# Main.net
KiCad netlist of a schematic drawn in Altium Designer
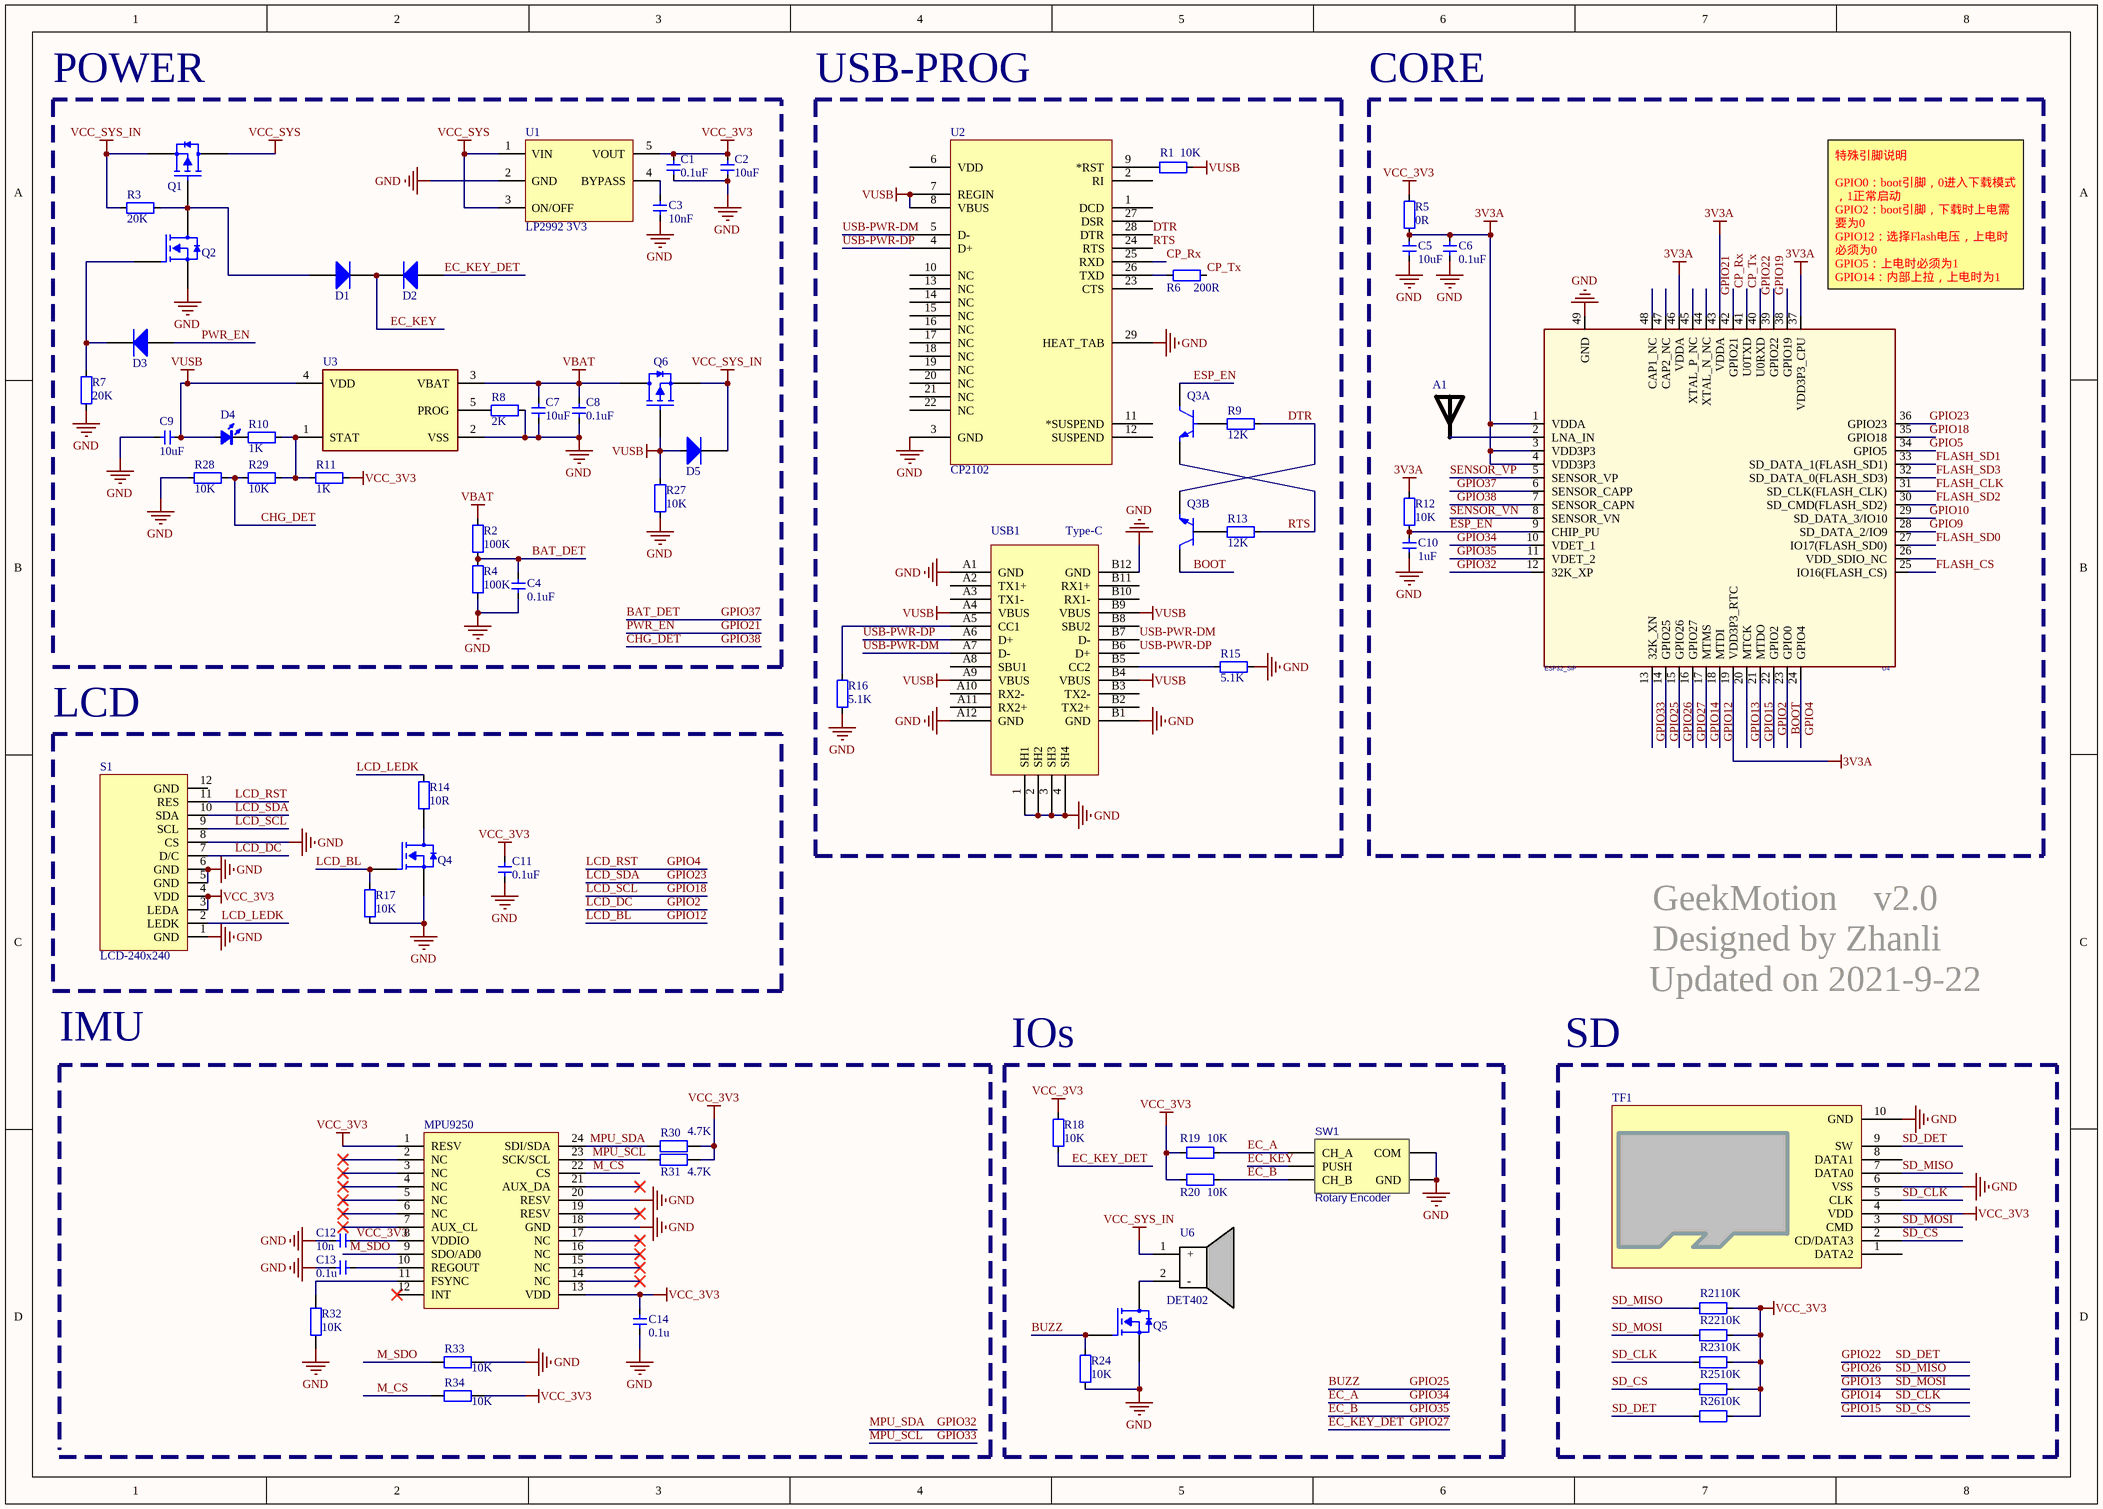
[diagram p0: Main.SchDoc]

(export (version "E")
  (design (tool "Eeschema 10.0.6"))
  (components
    (comp (ref "A1")
      (value "RAINSUN")
      (footprint "ANT-Rainsun-AN5120")
      (libsource (lib "MyPcbLib") (part "ANT-Rainsun-AP5120"))
    )
    (comp (ref "C1")
      (value "0.1uF")
      (footprint "CAP_0402")
      (description "Capacitor")
      (libsource (lib "MyPcbLib") (part "电容-0402"))
    )
    (comp (ref "C2")
      (value "10uF")
      (footprint "CAP_0402")
      (description "Capacitor")
      (libsource (lib "MyPcbLib") (part "电容-0402"))
    )
    (comp (ref "C3")
      (value "10nF")
      (footprint "CAP_0402")
      (description "Capacitor")
      (libsource (lib "MyPcbLib") (part "电容-0402"))
    )
    (comp (ref "C4")
      (value "0.1uF")
      (footprint "CAP_0402")
      (description "Capacitor")
      (libsource (lib "MyPcbLib") (part "电容-0402"))
    )
    (comp (ref "C5")
      (value "10uF")
      (footprint "CAP_0402")
      (description "Capacitor")
      (libsource (lib "MyPcbLib") (part "电容-0402"))
    )
    (comp (ref "C6")
      (value "0.1uF")
      (footprint "CAP_0402")
      (description "Capacitor")
      (libsource (lib "MyPcbLib") (part "电容-0402"))
    )
    (comp (ref "C7")
      (value "10uF")
      (footprint "CAP_0402")
      (description "Capacitor")
      (libsource (lib "MyPcbLib") (part "电容-0402"))
    )
    (comp (ref "C8")
      (value "0.1uF")
      (footprint "CAP_0402")
      (description "Capacitor")
      (libsource (lib "MyPcbLib") (part "电容-0402"))
    )
    (comp (ref "C9")
      (value "10uF")
      (footprint "CAP_0402")
      (description "Capacitor")
      (libsource (lib "MyPcbLib") (part "电容-0402"))
    )
    (comp (ref "C10")
      (value "1uF")
      (footprint "CAP_0402")
      (description "Capacitor")
      (libsource (lib "MyPcbLib") (part "电容-0402"))
    )
    (comp (ref "C11")
      (value "0.1uF")
      (footprint "CAP_0402")
      (description "Capacitor")
      (libsource (lib "MyPcbLib") (part "电容-0402"))
    )
    (comp (ref "C12")
      (value "10n")
      (footprint "CAP_0402")
      (description "Capacitor")
      (fields (field (name "Comment") "Cap_0603"))
      (libsource (lib "SmartIMU") (part "Cap_0603"))
    )
    (comp (ref "C13")
      (value "0.1u")
      (footprint "CAP_0402")
      (description "Capacitor")
      (fields (field (name "Comment") "Cap_0603"))
      (libsource (lib "SmartIMU") (part "Cap_0603"))
    )
    (comp (ref "C14")
      (value "0.1u")
      (footprint "CAP_0402")
      (description "Capacitor")
      (fields (field (name "Comment") "Cap_0603"))
      (libsource (lib "SmartIMU") (part "Cap_0603"))
    )
    (comp (ref "D1")
      (value "二极管-5819W")
      (footprint "SOD-323")
      (description "40V")
      (libsource (lib "MyPcbLib") (part "二极管-5819W"))
    )
    (comp (ref "D2")
      (value "二极管-5819W")
      (footprint "SOD-323")
      (description "40V")
      (libsource (lib "MyPcbLib") (part "二极管-5819W"))
    )
    (comp (ref "D3")
      (value "二极管-5819W")
      (footprint "SOD-323")
      (description "40V")
      (libsource (lib "MyPcbLib") (part "二极管-5819W"))
    )
    (comp (ref "D4")
      (value "color?")
      (footprint "LED_0402_RED")
      (description "LED")
      (libsource (lib "KitSprout") (part "LED_0402"))
    )
    (comp (ref "D5")
      (value "二极管-5819W")
      (footprint "SOD-323")
      (description "40V")
      (libsource (lib "Peak") (part "二极管-5819W"))
    )
    (comp (ref "MPU9250")
      (value "MPU9250")
      (footprint "GeekIMUv1:QFN_P0.4_24")
      (description "Sensor Motion")
      (libsource (lib "GeekIMU") (part "MPU925x"))
    )
    (comp (ref "Q1")
      (value "AO3401A")
      (footprint "SOT23-3")
      (description "P-MOS")
      (libsource (lib "MyPcbLib") (part "AO3401A"))
    )
    (comp (ref "Q2")
      (value "AO3400A")
      (footprint "SOT23-3")
      (description "N-MOS")
      (libsource (lib "MyPcbLib") (part "AO3400A"))
    )
    (comp (ref "Q3")
      (value "BC847BVC-7")
      (footprint "SOT563-6")
      (libsource (lib "MyPcbLib") (part "BC847BVC-7"))
    )
    (comp (ref "Q4")
      (value "AO3400A")
      (footprint "SOT23-3")
      (description "N-MOS")
      (libsource (lib "MyPcbLib") (part "AO3400A"))
    )
    (comp (ref "Q5")
      (value "AO3400A")
      (footprint "SOT23-3")
      (description "N-MOS")
      (libsource (lib "MyPcbLib") (part "AO3400A"))
    )
    (comp (ref "Q6")
      (value "AO3401A")
      (footprint "SOT23-3")
      (description "P-MOS")
      (libsource (lib "MyPcbLib") (part "AO3401A"))
    )
    (comp (ref "R1")
      (value "10K")
      (footprint "RES_0402")
      (description "Resistor")
      (libsource (lib "") (part "电阻-0402_1"))
    )
    (comp (ref "R2")
      (value "100K")
      (footprint "RES_0402")
      (description "Resistor")
      (libsource (lib "") (part "电阻-0402_2"))
    )
    (comp (ref "R3")
      (value "20K")
      (footprint "RES_0402")
      (description "Resistor")
      (libsource (lib "MyPcbLib") (part "电阻-0402"))
    )
    (comp (ref "R4")
      (value "100K")
      (footprint "RES_0402")
      (description "Resistor")
      (libsource (lib "") (part "电阻-0402_2"))
    )
    (comp (ref "R5")
      (value "0R")
      (footprint "RES_0402")
      (description "Resistor")
      (libsource (lib "") (part "电阻-0402_3"))
    )
    (comp (ref "R6")
      (value "200R")
      (footprint "RES_0402")
      (description "Resistor")
      (libsource (lib "") (part "电阻-0402_1"))
    )
    (comp (ref "R7")
      (value "20K")
      (footprint "RES_0402")
      (description "Resistor")
      (libsource (lib "") (part "电阻-0402_2"))
    )
    (comp (ref "R8")
      (value "2K")
      (footprint "RES_0402")
      (description "Resistor")
      (libsource (lib "MyPcbLib") (part "电阻-0402"))
    )
    (comp (ref "R9")
      (value "12K")
      (footprint "RES_0402")
      (description "Resistor")
      (libsource (lib "") (part "电阻-0402_1"))
    )
    (comp (ref "R10")
      (value "1K")
      (footprint "RES_0402")
      (description "Resistor")
      (libsource (lib "MyPcbLib") (part "电阻-0402"))
    )
    (comp (ref "R11")
      (value "1K")
      (footprint "RES_0402")
      (description "Resistor")
      (libsource (lib "MyPcbLib") (part "电阻-0402"))
    )
    (comp (ref "R12")
      (value "10K")
      (footprint "RES_0402")
      (description "Resistor")
      (libsource (lib "") (part "电阻-0402_3"))
    )
    (comp (ref "R13")
      (value "12K")
      (footprint "RES_0402")
      (description "Resistor")
      (libsource (lib "") (part "电阻-0402_1"))
    )
    (comp (ref "R14")
      (value "10R")
      (footprint "RES_0402")
      (description "Resistor")
      (libsource (lib "") (part "电阻-0402_2"))
    )
    (comp (ref "R15")
      (value "5.1K")
      (footprint "RES_0402")
      (description "Resistor")
      (libsource (lib "") (part "电阻-0402_1"))
    )
    (comp (ref "R16")
      (value "5.1K")
      (footprint "RES_0402")
      (description "Resistor")
      (libsource (lib "") (part "电阻-0402_3"))
    )
    (comp (ref "R17")
      (value "10K")
      (footprint "RES_0402")
      (description "Resistor")
      (libsource (lib "") (part "电阻-0402_2"))
    )
    (comp (ref "R18")
      (value "10K")
      (footprint "RES_0402")
      (description "Resistor")
      (libsource (lib "") (part "电阻-0402_3"))
    )
    (comp (ref "R19")
      (value "10K")
      (footprint "RES_0402")
      (description "Resistor")
      (libsource (lib "") (part "电阻-0402_1"))
    )
    (comp (ref "R20")
      (value "10K")
      (footprint "RES_0402")
      (description "Resistor")
      (libsource (lib "") (part "电阻-0402_1"))
    )
    (comp (ref "R21")
      (value "10K")
      (footprint "RES_0402")
      (description "Resistor")
      (libsource (lib "") (part "电阻-0402_1"))
    )
    (comp (ref "R22")
      (value "10K")
      (footprint "RES_0402")
      (description "Resistor")
      (libsource (lib "") (part "电阻-0402_1"))
    )
    (comp (ref "R23")
      (value "10K")
      (footprint "RES_0402")
      (description "Resistor")
      (libsource (lib "") (part "电阻-0402_1"))
    )
    (comp (ref "R24")
      (value "10K")
      (footprint "RES_0402")
      (description "Resistor")
      (libsource (lib "") (part "电阻-0402_2"))
    )
    (comp (ref "R25")
      (value "10K")
      (footprint "RES_0402")
      (description "Resistor")
      (libsource (lib "") (part "电阻-0402_1"))
    )
    (comp (ref "R26")
      (value "10K")
      (footprint "RES_0402")
      (description "Resistor")
      (libsource (lib "") (part "电阻-0402_1"))
    )
    (comp (ref "R27")
      (value "10K")
      (footprint "RES_0402")
      (description "Resistor")
      (libsource (lib "") (part "电阻-0402_2"))
    )
    (comp (ref "R28")
      (value "10K")
      (footprint "Peak:RES_0402")
      (description "Resistor")
      (libsource (lib "") (part "电阻-0402_1"))
    )
    (comp (ref "R29")
      (value "10K")
      (footprint "RES_0402")
      (description "Resistor")
      (libsource (lib "") (part "电阻-0402_1"))
    )
    (comp (ref "R30")
      (value "4.7K")
      (footprint "Peak:RES_0402")
      (description "Resistor")
      (fields (field (name "PUBLISHER") "Altium Limited"))
      (libsource (lib "Peak") (part "Res2"))
    )
    (comp (ref "R31")
      (value "4.7K")
      (footprint "Peak:RES_0402")
      (description "Resistor")
      (fields (field (name "PUBLISHER") "Altium Limited"))
      (libsource (lib "Peak") (part "Res2"))
    )
    (comp (ref "R32")
      (value "10K")
      (footprint "Peak:RES_0402")
      (description "Resistor")
      (fields (field (name "PUBLISHER") "Altium Limited"))
      (libsource (lib "") (part "Res2_1"))
    )
    (comp (ref "R33")
      (value "10K")
      (footprint "Peak:RES_0402")
      (description "Resistor")
      (fields (field (name "PUBLISHER") "Altium Limited"))
      (libsource (lib "Peak") (part "Res2"))
    )
    (comp (ref "R34")
      (value "10K")
      (footprint "Peak:RES_0402")
      (description "Resistor")
      (fields (field (name "PUBLISHER") "Altium Limited"))
      (libsource (lib "Peak") (part "Res2"))
    )
    (comp (ref "S1")
      (value "LCD-240x240")
      (footprint "LCD-240x240-FlUSH-154")
      (description "显示屏")
      (libsource (lib "mLib") (part "LCD-240x240"))
    )
    (comp (ref "SW1")
      (value "Rotary Encoder")
      (footprint "SIQ-02FVS3")
      (fields
        (field (name "BOM_SUPPLIER PART") "C1322543")
        (field (name "BOM_MANUFACTURER PART") "EC11E1534443")
        (field (name "CONTRIBUTOR") "LCSC")
      )
      (libsource (lib "MyPcbLib") (part "Rotary Encoder"))
    )
    (comp (ref "TF1")
      (value "TF")
      (footprint "TF-SOCKET")
      (description "8脚自弹")
      (libsource (lib "MyPcbLib") (part "TF卡座"))
    )
    (comp (ref "U1")
      (value "LP2992 3V3")
      (footprint "SOT23-5")
      (description "LDO")
      (libsource (lib "mLib") (part "LP2992"))
    )
    (comp (ref "U2")
      (value "CP2102")
      (footprint "QFN-28")
      (description "USB转TTL")
      (libsource (lib "mLib") (part "CP2102"))
    )
    (comp (ref "U3")
      (value "MCP73831T")
      (footprint "SOT23-5")
      (libsource (lib "MyPcbLib") (part "MCP73831T"))
    )
    (comp (ref "U4")
      (value "ESP32_SIP")
      (footprint "QFN-48_7X7")
      (libsource (lib "mLib") (part "ESP32-PICO"))
    )
    (comp (ref "U6") (value "DET402") (footprint "DET402") (libsource (lib "MyPcbLib") (part "DET402")))
    (comp (ref "USB1")
      (value "Type-C")
      (footprint "Type-C-TOP")
      (libsource (lib "MyPcbLib") (part "USB-Type-C-TOP"))
    )
  )
  (nets
    (net (code "1") (name "/BAT_DET") (class "Default")
      (node (ref "C4") (pin "2") (pinfunction "2_2") (pintype "passive"))
      (node (ref "R2") (pin "1") (pinfunction "1_1") (pintype "passive"))
      (node (ref "R4") (pin "2") (pinfunction "2_2") (pintype "passive"))
      (node (ref "U4") (pin "6") (pinfunction "SENSOR_CAPP_6") (pintype "passive"))
    )
    (net (code "2") (name "/BOOT") (class "Default")
      (node (ref "Q3") (pin "3") (pinfunction "C2_3") (pintype "passive"))
      (node (ref "U4") (pin "23") (pinfunction "GPIO0_23") (pintype "passive"))
    )
    (net (code "3") (name "/BUZZ") (class "Default")
      (node (ref "Q5") (pin "1") (pinfunction "G_1") (pintype "passive"))
      (node (ref "R24") (pin "2") (pinfunction "2_2") (pintype "passive"))
      (node (ref "U4") (pin "14") (pinfunction "GPIO25_14") (pintype "passive"))
    )
    (net (code "4") (name "/CHG_DET") (class "Default")
      (node (ref "R28") (pin "1") (pinfunction "1_1") (pintype "passive"))
      (node (ref "R29") (pin "2") (pinfunction "2_2") (pintype "passive"))
      (node (ref "U4") (pin "7") (pinfunction "SENSOR_CAPN_7") (pintype "passive"))
    )
    (net (code "5") (name "/CP_Rx") (class "Default")
      (node (ref "U2") (pin "25") (pinfunction "RXD_25") (pintype "passive"))
      (node (ref "U4") (pin "41") (pinfunction "U0TXD_41") (pintype "power_in"))
    )
    (net (code "6") (name "/CP_Tx") (class "Default")
      (node (ref "R6") (pin "1") (pinfunction "1_1") (pintype "passive"))
      (node (ref "U4") (pin "40") (pinfunction "U0RXD_40") (pintype "power_in"))
    )
    (net (code "7") (name "/DTR") (class "Default")
      (node (ref "Q3") (pin "4") (pinfunction "E2_4") (pintype "passive"))
      (node (ref "R9") (pin "1") (pinfunction "1_1") (pintype "passive"))
      (node (ref "U2") (pin "28") (pinfunction "DTR_28") (pintype "passive"))
    )
    (net (code "8") (name "/EC_A") (class "Default")
      (node (ref "R19") (pin "1") (pinfunction "1_1") (pintype "passive"))
      (node (ref "SW1") (pin "1") (pinfunction "CH_A_1") (pintype "passive"))
      (node (ref "U4") (pin "10") (pinfunction "VDET_1_10") (pintype "passive"))
    )
    (net (code "9") (name "/EC_B") (class "Default")
      (node (ref "R20") (pin "1") (pinfunction "1_1") (pintype "passive"))
      (node (ref "SW1") (pin "4") (pinfunction "CH_B_4") (pintype "passive"))
      (node (ref "U4") (pin "11") (pinfunction "VDET_2_11") (pintype "passive"))
    )
    (net (code "10") (name "/EC_KEY") (class "Default")
      (node (ref "D1") (pin "2") (pinfunction "K_2") (pintype "passive"))
      (node (ref "D2") (pin "2") (pinfunction "K_2") (pintype "passive"))
      (node (ref "SW1") (pin "2") (pinfunction "PUSH_2") (pintype "passive"))
    )
    (net (code "11") (name "/EC_KEY_DET") (class "Default")
      (node (ref "D2") (pin "1") (pinfunction "A_1") (pintype "passive"))
      (node (ref "R18") (pin "2") (pinfunction "2_2") (pintype "passive"))
      (node (ref "U4") (pin "16") (pinfunction "GPIO27_16") (pintype "passive"))
    )
    (net (code "12") (name "/ESP_EN") (class "Default")
      (node (ref "C10") (pin "1") (pinfunction "1_1") (pintype "passive"))
      (node (ref "Q3") (pin "6") (pinfunction "C1_6") (pintype "passive"))
      (node (ref "R12") (pin "2") (pinfunction "2_2") (pintype "passive"))
      (node (ref "U4") (pin "9") (pinfunction "CHIP_PU_9") (pintype "passive"))
    )
    (net (code "13") (name "/FLASH_CLK") (class "Default")
      (node (ref "U4") (pin "31") (pinfunction "SD_CLK(FLASH_CLK)_31") (pintype "passive"))
    )
    (net (code "14") (name "/FLASH_CS") (class "Default")
      (node (ref "U4") (pin "25") (pinfunction "IO16(FLASH_CS)_25") (pintype "passive"))
    )
    (net (code "15") (name "/FLASH_SD0") (class "Default")
      (node (ref "U4") (pin "27") (pinfunction "IO17(FLASH_SD0)_27") (pintype "passive"))
    )
    (net (code "16") (name "/FLASH_SD1") (class "Default")
      (node (ref "U4") (pin "33") (pinfunction "SD_DATA_1(FLASH_SD1)_33") (pintype "passive"))
    )
    (net (code "17") (name "/FLASH_SD2") (class "Default")
      (node (ref "U4") (pin "30") (pinfunction "SD_CMD(FLASH_SD2)_30") (pintype "passive"))
    )
    (net (code "18") (name "/FLASH_SD3") (class "Default")
      (node (ref "U4") (pin "32") (pinfunction "SD_DATA_0(FLASH_SD3)_32") (pintype "passive"))
    )
    (net (code "19") (name "/GPIO2") (class "Default")
      (node (ref "S1") (pin "7") (pinfunction "D/C_7") (pintype "passive"))
      (node (ref "U4") (pin "22") (pinfunction "GPIO2_22") (pintype "passive"))
    )
    (net (code "20") (name "/GPIO4") (class "Default")
      (node (ref "S1") (pin "11") (pinfunction "RES_11") (pintype "passive"))
      (node (ref "U4") (pin "24") (pinfunction "GPIO4_24") (pintype "passive"))
    )
    (net (code "21") (name "/GPIO5") (class "Default")
      (node (ref "U4") (pin "34") (pinfunction "GPIO5_34") (pintype "passive"))
    )
    (net (code "22") (name "/GPIO9") (class "Default")
      (node (ref "U4") (pin "28") (pinfunction "SD_DATA_2/IO9_28") (pintype "passive"))
    )
    (net (code "23") (name "/GPIO10") (class "Default")
      (node (ref "U4") (pin "29") (pinfunction "SD_DATA_3/IO10_29") (pintype "passive"))
    )
    (net (code "24") (name "/GPIO12") (class "Default")
      (node (ref "Q4") (pin "1") (pinfunction "G_1") (pintype "passive"))
      (node (ref "R17") (pin "2") (pinfunction "2_2") (pintype "passive"))
      (node (ref "U4") (pin "18") (pinfunction "MTDI_18") (pintype "passive"))
    )
    (net (code "25") (name "/GPIO13") (class "Default")
      (node (ref "R22") (pin "2") (pinfunction "2_2") (pintype "passive"))
      (node (ref "TF1") (pin "3") (pinfunction "CMD_3") (pintype "passive"))
      (node (ref "U4") (pin "20") (pinfunction "MTCK_20") (pintype "passive"))
    )
    (net (code "26") (name "/GPIO14") (class "Default")
      (node (ref "R23") (pin "2") (pinfunction "2_2") (pintype "passive"))
      (node (ref "TF1") (pin "5") (pinfunction "CLK_5") (pintype "passive"))
      (node (ref "U4") (pin "17") (pinfunction "MTMS_17") (pintype "passive"))
    )
    (net (code "27") (name "/GPIO15") (class "Default")
      (node (ref "R25") (pin "2") (pinfunction "2_2") (pintype "passive"))
      (node (ref "TF1") (pin "2") (pinfunction "CD/DATA3_2") (pintype "passive"))
      (node (ref "U4") (pin "21") (pinfunction "MTDO_21") (pintype "passive"))
    )
    (net (code "28") (name "/GPIO18") (class "Default")
      (node (ref "S1") (pin "9") (pinfunction "SCL_9") (pintype "passive"))
      (node (ref "U4") (pin "35") (pinfunction "GPIO18_35") (pintype "passive"))
    )
    (net (code "29") (name "/GPIO19") (class "Default")
      (node (ref "U4") (pin "38") (pinfunction "GPIO19_38") (pintype "passive"))
    )
    (net (code "30") (name "/GPIO21") (class "Default")
      (node (ref "D3") (pin "1") (pinfunction "A_1") (pintype "passive"))
      (node (ref "U4") (pin "42") (pinfunction "GPIO21_42") (pintype "passive"))
    )
    (net (code "31") (name "/GPIO22") (class "Default")
      (node (ref "R26") (pin "2") (pinfunction "2_2") (pintype "passive"))
      (node (ref "TF1") (pin "9") (pinfunction "SW_9") (pintype "passive"))
      (node (ref "U4") (pin "39") (pinfunction "GPIO22_39") (pintype "passive"))
    )
    (net (code "32") (name "/GPIO23") (class "Default")
      (node (ref "S1") (pin "10") (pinfunction "SDA_10") (pintype "passive"))
      (node (ref "U4") (pin "36") (pinfunction "GPIO23_36") (pintype "passive"))
    )
    (net (code "33") (name "/GPIO26") (class "Default")
      (node (ref "R21") (pin "2") (pinfunction "2_2") (pintype "passive"))
      (node (ref "TF1") (pin "7") (pinfunction "DATA0_7") (pintype "passive"))
      (node (ref "U4") (pin "15") (pinfunction "GPIO26_15") (pintype "passive"))
    )
    (net (code "34") (name "/GPIO32") (class "Default")
      (node (ref "MPU9250") (pin "24") (pinfunction "SDI/SDA_24") (pintype "passive"))
      (node (ref "R30") (pin "2") (pinfunction "2_2") (pintype "passive"))
      (node (ref "U4") (pin "12") (pinfunction "32K_XP_12") (pintype "passive"))
    )
    (net (code "35") (name "/GPIO33") (class "Default")
      (node (ref "MPU9250") (pin "23") (pinfunction "SCK/SCL_23") (pintype "passive"))
      (node (ref "R31") (pin "2") (pinfunction "2_2") (pintype "passive"))
      (node (ref "U4") (pin "13") (pinfunction "32K_XN_13") (pintype "passive"))
    )
    (net (code "36") (name "/LCD_LEDK") (class "Default")
      (node (ref "R14") (pin "2") (pinfunction "2_2") (pintype "passive"))
      (node (ref "S1") (pin "2") (pinfunction "LEDK_2") (pintype "passive"))
    )
    (net (code "37") (name "/M_CS") (class "Default")
      (node (ref "MPU9250") (pin "22") (pinfunction "CS_22") (pintype "passive"))
      (node (ref "R34") (pin "2") (pinfunction "2_2") (pintype "passive"))
    )
    (net (code "38") (name "/M_SDO") (class "Default")
      (node (ref "MPU9250") (pin "9") (pinfunction "SDO/AD0_9") (pintype "passive"))
      (node (ref "R33") (pin "2") (pinfunction "2_2") (pintype "passive"))
    )
    (net (code "39") (name "/RTS") (class "Default")
      (node (ref "Q3") (pin "1") (pinfunction "E1_1") (pintype "passive"))
      (node (ref "R13") (pin "1") (pinfunction "1_1") (pintype "passive"))
      (node (ref "U2") (pin "24") (pinfunction "RTS_24") (pintype "passive"))
    )
    (net (code "40") (name "/SENSOR_VN") (class "Default")
      (node (ref "U4") (pin "8") (pinfunction "SENSOR_VN_8") (pintype "passive"))
    )
    (net (code "41") (name "/SENSOR_VP") (class "Default")
      (node (ref "U4") (pin "5") (pinfunction "SENSOR_VP_5") (pintype "passive"))
    )
    (net (code "42") (name "/USB-PWR-DM") (class "Default")
      (node (ref "U2") (pin "5") (pinfunction "D-_5") (pintype "passive"))
      (node (ref "USB1") (pin "A7") (pinfunction "D-_A7") (pintype "passive"))
      (node (ref "USB1") (pin "B7") (pinfunction "D-_B7") (pintype "passive"))
    )
    (net (code "43") (name "/USB-PWR-DP") (class "Default")
      (node (ref "U2") (pin "4") (pinfunction "D+_4") (pintype "passive"))
      (node (ref "USB1") (pin "A6") (pinfunction "D+_A6") (pintype "passive"))
      (node (ref "USB1") (pin "B6") (pinfunction "D+_B6") (pintype "passive"))
    )
    (net (code "44") (name "3V3A") (class "Default")
      (node (ref "C5") (pin "2") (pinfunction "2_2") (pintype "passive"))
      (node (ref "C6") (pin "2") (pinfunction "2_2") (pintype "passive"))
      (node (ref "R12") (pin "1") (pinfunction "1_1") (pintype "passive"))
      (node (ref "R5") (pin "2") (pinfunction "2_2") (pintype "passive"))
      (node (ref "U4") (pin "1") (pinfunction "VDDA_1") (pintype "power_in"))
      (node (ref "U4") (pin "19") (pinfunction "VDD3P3_RTC_19") (pintype "power_in"))
      (node (ref "U4") (pin "3") (pinfunction "VDD3P3_3") (pintype "power_in"))
      (node (ref "U4") (pin "37") (pinfunction "VDD3P3_CPU_37") (pintype "power_in"))
      (node (ref "U4") (pin "4") (pinfunction "VDD3P3_4") (pintype "power_in"))
      (node (ref "U4") (pin "43") (pinfunction "VDDA_43") (pintype "power_in"))
      (node (ref "U4") (pin "46") (pinfunction "VDDA_46") (pintype "power_in"))
    )
    (net (code "45") (name "GND") (class "Default")
      (node (ref "C1") (pin "1") (pinfunction "1_1") (pintype "passive"))
      (node (ref "C10") (pin "2") (pinfunction "2_2") (pintype "passive"))
      (node (ref "C11") (pin "1") (pinfunction "1_1") (pintype "passive"))
      (node (ref "C12") (pin "1") (pinfunction "1_1") (pintype "passive"))
      (node (ref "C13") (pin "1") (pinfunction "1_1") (pintype "passive"))
      (node (ref "C14") (pin "2") (pinfunction "2_2") (pintype "passive"))
      (node (ref "C2") (pin "1") (pinfunction "1_1") (pintype "passive"))
      (node (ref "C3") (pin "1") (pinfunction "1_1") (pintype "passive"))
      (node (ref "C4") (pin "1") (pinfunction "1_1") (pintype "passive"))
      (node (ref "C5") (pin "1") (pinfunction "1_1") (pintype "passive"))
      (node (ref "C6") (pin "1") (pinfunction "1_1") (pintype "passive"))
      (node (ref "C7") (pin "1") (pinfunction "1_1") (pintype "passive"))
      (node (ref "C8") (pin "1") (pinfunction "1_1") (pintype "passive"))
      (node (ref "C9") (pin "1") (pinfunction "1_1") (pintype "passive"))
      (node (ref "MPU9250") (pin "18") (pinfunction "GND_18") (pintype "passive"))
      (node (ref "MPU9250") (pin "20") (pinfunction "RESV_20") (pintype "passive"))
      (node (ref "Q2") (pin "2") (pinfunction "S_2") (pintype "passive"))
      (node (ref "Q4") (pin "2") (pinfunction "S_2") (pintype "passive"))
      (node (ref "Q5") (pin "2") (pinfunction "S_2") (pintype "passive"))
      (node (ref "R15") (pin "1") (pinfunction "1_1") (pintype "passive"))
      (node (ref "R16") (pin "2") (pinfunction "2_2") (pintype "passive"))
      (node (ref "R17") (pin "1") (pinfunction "1_1") (pintype "passive"))
      (node (ref "R24") (pin "1") (pinfunction "1_1") (pintype "passive"))
      (node (ref "R27") (pin "1") (pinfunction "1_1") (pintype "passive"))
      (node (ref "R28") (pin "2") (pinfunction "2_2") (pintype "passive"))
      (node (ref "R32") (pin "2") (pinfunction "2_2") (pintype "passive"))
      (node (ref "R33") (pin "1") (pinfunction "1_1") (pintype "passive"))
      (node (ref "R4") (pin "1") (pinfunction "1_1") (pintype "passive"))
      (node (ref "R7") (pin "1") (pinfunction "1_1") (pintype "passive"))
      (node (ref "R8") (pin "2") (pinfunction "2_2") (pintype "passive"))
      (node (ref "S1") (pin "1") (pinfunction "GND_1") (pintype "passive"))
      (node (ref "S1") (pin "5") (pinfunction "GND_5") (pintype "passive"))
      (node (ref "S1") (pin "6") (pinfunction "GND_6") (pintype "passive"))
      (node (ref "S1") (pin "8") (pinfunction "CS_8") (pintype "passive"))
      (node (ref "SW1") (pin "3") (pinfunction "COM_3") (pintype "passive"))
      (node (ref "SW1") (pin "5") (pinfunction "GND_5") (pintype "passive"))
      (node (ref "TF1") (pin "10") (pinfunction "GND_10") (pintype "passive"))
      (node (ref "TF1") (pin "6") (pinfunction "VSS_6") (pintype "passive"))
      (node (ref "U1") (pin "2") (pinfunction "GND_2") (pintype "passive"))
      (node (ref "U2") (pin "29") (pinfunction "HEAT_TAB_29") (pintype "passive"))
      (node (ref "U2") (pin "3") (pinfunction "GND_3") (pintype "passive"))
      (node (ref "U3") (pin "2") (pinfunction "VSS_2") (pintype "power_in"))
      (node (ref "U4") (pin "49") (pinfunction "GND_49") (pintype "power_in"))
      (node (ref "USB1") (pin "1") (pinfunction "SH1_1") (pintype "passive"))
      (node (ref "USB1") (pin "2") (pinfunction "SH2_2") (pintype "passive"))
      (node (ref "USB1") (pin "3") (pinfunction "SH3_3") (pintype "passive"))
      (node (ref "USB1") (pin "4") (pinfunction "SH4_4") (pintype "passive"))
      (node (ref "USB1") (pin "A1") (pinfunction "GND_A1") (pintype "passive"))
      (node (ref "USB1") (pin "A12") (pinfunction "GND_A12") (pintype "passive"))
      (node (ref "USB1") (pin "B1") (pinfunction "GND_B1") (pintype "passive"))
      (node (ref "USB1") (pin "B12") (pinfunction "GND_B12") (pintype "passive"))
    )
    (net (code "46") (name "Net-(D1-A)") (class "Default")
      (node (ref "D1") (pin "1") (pinfunction "A_1") (pintype "passive"))
      (node (ref "Q1") (pin "1") (pinfunction "G_1") (pintype "passive"))
      (node (ref "Q2") (pin "3") (pinfunction "D_3") (pintype "passive"))
      (node (ref "R3") (pin "2") (pinfunction "2_2") (pintype "passive"))
    )
    (net (code "47") (name "Net-(D3-K)") (class "Default")
      (node (ref "D3") (pin "2") (pinfunction "K_2") (pintype "passive"))
      (node (ref "Q2") (pin "1") (pinfunction "G_1") (pintype "passive"))
      (node (ref "R7") (pin "2") (pinfunction "2_2") (pintype "passive"))
    )
    (net (code "48") (name "Net-(D4-K)") (class "Default")
      (node (ref "D4") (pin "2") (pinfunction "K_2") (pintype "passive"))
      (node (ref "R10") (pin "1") (pinfunction "1_1") (pintype "passive"))
    )
    (net (code "49") (name "Net-(MPU9250-FSYNC)") (class "Default")
      (node (ref "MPU9250") (pin "11") (pinfunction "FSYNC_11") (pintype "passive"))
      (node (ref "R32") (pin "1") (pinfunction "1_1") (pintype "passive"))
    )
    (net (code "50") (name "Net-(MPU9250-REGOUT)") (class "Default")
      (node (ref "C13") (pin "2") (pinfunction "2_2") (pintype "passive"))
      (node (ref "MPU9250") (pin "10") (pinfunction "REGOUT_10") (pintype "passive"))
    )
    (net (code "51") (name "Net-(Q3A-B1)") (class "Default")
      (node (ref "Q3") (pin "2") (pinfunction "B1_2") (pintype "passive"))
      (node (ref "R9") (pin "2") (pinfunction "2_2") (pintype "passive"))
    )
    (net (code "52") (name "Net-(Q3B-B2)") (class "Default")
      (node (ref "Q3") (pin "5") (pinfunction "B2_5") (pintype "passive"))
      (node (ref "R13") (pin "2") (pinfunction "2_2") (pintype "passive"))
    )
    (net (code "53") (name "Net-(Q4-D)") (class "Default")
      (node (ref "Q4") (pin "3") (pinfunction "D_3") (pintype "passive"))
      (node (ref "R14") (pin "1") (pinfunction "1_1") (pintype "passive"))
    )
    (net (code "54") (name "Net-(Q5-D)") (class "Default")
      (node (ref "Q5") (pin "3") (pinfunction "D_3") (pintype "passive"))
      (node (ref "U6") (pin "2") (pinfunction "-_2") (pintype "passive"))
    )
    (net (code "55") (name "Net-(U1-BYPASS)") (class "Default")
      (node (ref "C3") (pin "2") (pinfunction "2_2") (pintype "passive"))
      (node (ref "U1") (pin "4") (pinfunction "BYPASS_4") (pintype "passive"))
    )
    (net (code "56") (name "Net-(U2-*RST)") (class "Default")
      (node (ref "R1") (pin "2") (pinfunction "2_2") (pintype "passive"))
      (node (ref "U2") (pin "9") (pinfunction "*RST_9") (pintype "passive"))
    )
    (net (code "57") (name "Net-(U2-TXD)") (class "Default")
      (node (ref "R6") (pin "2") (pinfunction "2_2") (pintype "passive"))
      (node (ref "U2") (pin "26") (pinfunction "TXD_26") (pintype "passive"))
    )
    (net (code "58") (name "Net-(U3-PROG)") (class "Default")
      (node (ref "R8") (pin "1") (pinfunction "1_1") (pintype "passive"))
      (node (ref "U3") (pin "5") (pinfunction "PROG_5") (pintype "passive"))
    )
    (net (code "59") (name "Net-(U3-STAT)") (class "Default")
      (node (ref "R10") (pin "2") (pinfunction "2_2") (pintype "passive"))
      (node (ref "R11") (pin "1") (pinfunction "1_1") (pintype "passive"))
      (node (ref "R29") (pin "1") (pinfunction "1_1") (pintype "passive"))
      (node (ref "U3") (pin "1") (pinfunction "STAT_1") (pintype "passive"))
    )
    (net (code "60") (name "Net-(U4-LNA_IN)") (class "Default")
      (node (ref "A1") (pin "1") (pinfunction "1_1") (pintype "passive"))
      (node (ref "U4") (pin "2") (pinfunction "LNA_IN_2") (pintype "passive"))
    )
    (net (code "61") (name "Net-(USB1-CC1)") (class "Default")
      (node (ref "R16") (pin "1") (pinfunction "1_1") (pintype "passive"))
      (node (ref "USB1") (pin "A5") (pinfunction "CC1_A5") (pintype "passive"))
    )
    (net (code "62") (name "Net-(USB1-CC2)") (class "Default")
      (node (ref "R15") (pin "2") (pinfunction "2_2") (pintype "passive"))
      (node (ref "USB1") (pin "B5") (pinfunction "CC2_B5") (pintype "passive"))
    )
    (net (code "63") (name "VBAT") (class "Default")
      (node (ref "C7") (pin "2") (pinfunction "2_2") (pintype "passive"))
      (node (ref "C8") (pin "2") (pinfunction "2_2") (pintype "passive"))
      (node (ref "Q6") (pin "3") (pinfunction "D_3") (pintype "passive"))
      (node (ref "R2") (pin "2") (pinfunction "2_2") (pintype "passive"))
      (node (ref "U3") (pin "3") (pinfunction "VBAT_3") (pintype "power_in"))
    )
    (net (code "64") (name "VCC_3V3") (class "Default")
      (node (ref "C1") (pin "2") (pinfunction "2_2") (pintype "passive"))
      (node (ref "C11") (pin "2") (pinfunction "2_2") (pintype "passive"))
      (node (ref "C12") (pin "2") (pinfunction "2_2") (pintype "passive"))
      (node (ref "C14") (pin "1") (pinfunction "1_1") (pintype "passive"))
      (node (ref "C2") (pin "2") (pinfunction "2_2") (pintype "passive"))
      (node (ref "MPU9250") (pin "1") (pinfunction "RESV_1") (pintype "passive"))
      (node (ref "MPU9250") (pin "13") (pinfunction "VDD_13") (pintype "passive"))
      (node (ref "MPU9250") (pin "8") (pinfunction "VDDIO_8") (pintype "passive"))
      (node (ref "R11") (pin "2") (pinfunction "2_2") (pintype "passive"))
      (node (ref "R18") (pin "1") (pinfunction "1_1") (pintype "passive"))
      (node (ref "R19") (pin "2") (pinfunction "2_2") (pintype "passive"))
      (node (ref "R20") (pin "2") (pinfunction "2_2") (pintype "passive"))
      (node (ref "R21") (pin "1") (pinfunction "1_1") (pintype "passive"))
      (node (ref "R22") (pin "1") (pinfunction "1_1") (pintype "passive"))
      (node (ref "R23") (pin "1") (pinfunction "1_1") (pintype "passive"))
      (node (ref "R25") (pin "1") (pinfunction "1_1") (pintype "passive"))
      (node (ref "R26") (pin "1") (pinfunction "1_1") (pintype "passive"))
      (node (ref "R30") (pin "1") (pinfunction "1_1") (pintype "passive"))
      (node (ref "R31") (pin "1") (pinfunction "1_1") (pintype "passive"))
      (node (ref "R34") (pin "1") (pinfunction "1_1") (pintype "passive"))
      (node (ref "R5") (pin "1") (pinfunction "1_1") (pintype "passive"))
      (node (ref "S1") (pin "3") (pinfunction "LEDA_3") (pintype "passive"))
      (node (ref "S1") (pin "4") (pinfunction "VDD_4") (pintype "passive"))
      (node (ref "TF1") (pin "4") (pinfunction "VDD_4") (pintype "passive"))
      (node (ref "U1") (pin "5") (pinfunction "VOUT_5") (pintype "passive"))
    )
    (net (code "65") (name "VCC_SYS") (class "Default")
      (node (ref "Q1") (pin "3") (pinfunction "D_3") (pintype "passive"))
      (node (ref "U1") (pin "1") (pinfunction "VIN_1") (pintype "passive"))
      (node (ref "U1") (pin "3") (pinfunction "ON/OFF_3") (pintype "passive"))
    )
    (net (code "66") (name "VCC_SYS_IN") (class "Default")
      (node (ref "D5") (pin "2") (pinfunction "K_2") (pintype "passive"))
      (node (ref "Q1") (pin "2") (pinfunction "S_2") (pintype "passive"))
      (node (ref "Q6") (pin "2") (pinfunction "S_2") (pintype "passive"))
      (node (ref "R3") (pin "1") (pinfunction "1_1") (pintype "passive"))
      (node (ref "U6") (pin "1") (pinfunction "+_1") (pintype "passive"))
    )
    (net (code "67") (name "VUSB") (class "Default")
      (node (ref "C9") (pin "2") (pinfunction "2_2") (pintype "passive"))
      (node (ref "D4") (pin "1") (pinfunction "A_1") (pintype "passive"))
      (node (ref "D5") (pin "1") (pinfunction "A_1") (pintype "passive"))
      (node (ref "Q6") (pin "1") (pinfunction "G_1") (pintype "passive"))
      (node (ref "R1") (pin "1") (pinfunction "1_1") (pintype "passive"))
      (node (ref "R27") (pin "2") (pinfunction "2_2") (pintype "passive"))
      (node (ref "U2") (pin "7") (pinfunction "REGIN_7") (pintype "passive"))
      (node (ref "U2") (pin "8") (pinfunction "VBUS_8") (pintype "passive"))
      (node (ref "U3") (pin "4") (pinfunction "VDD_4") (pintype "power_in"))
      (node (ref "USB1") (pin "A4") (pinfunction "VBUS_A4") (pintype "passive"))
      (node (ref "USB1") (pin "A9") (pinfunction "VBUS_A9") (pintype "passive"))
      (node (ref "USB1") (pin "B4") (pinfunction "VBUS_B4") (pintype "passive"))
      (node (ref "USB1") (pin "B9") (pinfunction "VBUS_B9") (pintype "passive"))
    )
    (net (code "68") (name "unconnected-(MPU9250-AUX_CL-Pad7)") (class "Default")
      (node (ref "MPU9250") (pin "7") (pinfunction "AUX_CL_7") (pintype "passive+no_connect"))
    )
    (net (code "69") (name "unconnected-(MPU9250-AUX_DA-Pad21)") (class "Default")
      (node (ref "MPU9250") (pin "21") (pinfunction "AUX_DA_21") (pintype "passive+no_connect"))
    )
    (net (code "70") (name "unconnected-(MPU9250-INT-Pad12)") (class "Default")
      (node (ref "MPU9250") (pin "12") (pinfunction "INT_12") (pintype "passive+no_connect"))
    )
    (net (code "71") (name "unconnected-(MPU9250-NC-Pad2)") (class "Default")
      (node (ref "MPU9250") (pin "2") (pinfunction "NC_2") (pintype "passive+no_connect"))
    )
    (net (code "72") (name "unconnected-(MPU9250-NC-Pad3)") (class "Default")
      (node (ref "MPU9250") (pin "3") (pinfunction "NC_3") (pintype "passive+no_connect"))
    )
    (net (code "73") (name "unconnected-(MPU9250-NC-Pad4)") (class "Default")
      (node (ref "MPU9250") (pin "4") (pinfunction "NC_4") (pintype "passive+no_connect"))
    )
    (net (code "74") (name "unconnected-(MPU9250-NC-Pad5)") (class "Default")
      (node (ref "MPU9250") (pin "5") (pinfunction "NC_5") (pintype "passive+no_connect"))
    )
    (net (code "75") (name "unconnected-(MPU9250-NC-Pad6)") (class "Default")
      (node (ref "MPU9250") (pin "6") (pinfunction "NC_6") (pintype "passive+no_connect"))
    )
    (net (code "76") (name "unconnected-(MPU9250-NC-Pad14)") (class "Default")
      (node (ref "MPU9250") (pin "14") (pinfunction "NC_14") (pintype "passive+no_connect"))
    )
    (net (code "77") (name "unconnected-(MPU9250-NC-Pad15)") (class "Default")
      (node (ref "MPU9250") (pin "15") (pinfunction "NC_15") (pintype "passive+no_connect"))
    )
    (net (code "78") (name "unconnected-(MPU9250-NC-Pad16)") (class "Default")
      (node (ref "MPU9250") (pin "16") (pinfunction "NC_16") (pintype "passive+no_connect"))
    )
    (net (code "79") (name "unconnected-(MPU9250-NC-Pad17)") (class "Default")
      (node (ref "MPU9250") (pin "17") (pinfunction "NC_17") (pintype "passive+no_connect"))
    )
    (net (code "80") (name "unconnected-(MPU9250-RESV-Pad19)") (class "Default")
      (node (ref "MPU9250") (pin "19") (pinfunction "RESV_19") (pintype "passive+no_connect"))
    )
    (net (code "81") (name "unconnected-(S1-GND-Pad12)") (class "Default")
      (node (ref "S1") (pin "12") (pinfunction "GND_12") (pintype "passive"))
    )
    (net (code "82") (name "unconnected-(TF1-DATA1-Pad8)") (class "Default")
      (node (ref "TF1") (pin "8") (pinfunction "DATA1_8") (pintype "passive"))
    )
    (net (code "83") (name "unconnected-(TF1-DATA2-Pad1)") (class "Default")
      (node (ref "TF1") (pin "1") (pinfunction "DATA2_1") (pintype "passive"))
    )
    (net (code "84") (name "unconnected-(U2-*SUSPEND-Pad11)") (class "Default")
      (node (ref "U2") (pin "11") (pinfunction "*SUSPEND_11") (pintype "passive"))
    )
    (net (code "85") (name "unconnected-(U2-CTS-Pad23)") (class "Default")
      (node (ref "U2") (pin "23") (pinfunction "CTS_23") (pintype "passive"))
    )
    (net (code "86") (name "unconnected-(U2-DCD-Pad1)") (class "Default")
      (node (ref "U2") (pin "1") (pinfunction "DCD_1") (pintype "passive"))
    )
    (net (code "87") (name "unconnected-(U2-DSR-Pad27)") (class "Default")
      (node (ref "U2") (pin "27") (pinfunction "DSR_27") (pintype "passive"))
    )
    (net (code "88") (name "unconnected-(U2-NC-Pad10)") (class "Default")
      (node (ref "U2") (pin "10") (pinfunction "NC_10") (pintype "passive"))
    )
    (net (code "89") (name "unconnected-(U2-NC-Pad13)") (class "Default")
      (node (ref "U2") (pin "13") (pinfunction "NC_13") (pintype "passive"))
    )
    (net (code "90") (name "unconnected-(U2-NC-Pad14)") (class "Default")
      (node (ref "U2") (pin "14") (pinfunction "NC_14") (pintype "passive"))
    )
    (net (code "91") (name "unconnected-(U2-NC-Pad15)") (class "Default")
      (node (ref "U2") (pin "15") (pinfunction "NC_15") (pintype "passive"))
    )
    (net (code "92") (name "unconnected-(U2-NC-Pad16)") (class "Default")
      (node (ref "U2") (pin "16") (pinfunction "NC_16") (pintype "passive"))
    )
    (net (code "93") (name "unconnected-(U2-NC-Pad17)") (class "Default")
      (node (ref "U2") (pin "17") (pinfunction "NC_17") (pintype "passive"))
    )
    (net (code "94") (name "unconnected-(U2-NC-Pad18)") (class "Default")
      (node (ref "U2") (pin "18") (pinfunction "NC_18") (pintype "passive"))
    )
    (net (code "95") (name "unconnected-(U2-NC-Pad19)") (class "Default")
      (node (ref "U2") (pin "19") (pinfunction "NC_19") (pintype "passive"))
    )
    (net (code "96") (name "unconnected-(U2-NC-Pad20)") (class "Default")
      (node (ref "U2") (pin "20") (pinfunction "NC_20") (pintype "passive"))
    )
    (net (code "97") (name "unconnected-(U2-NC-Pad21)") (class "Default")
      (node (ref "U2") (pin "21") (pinfunction "NC_21") (pintype "passive"))
    )
    (net (code "98") (name "unconnected-(U2-NC-Pad22)") (class "Default")
      (node (ref "U2") (pin "22") (pinfunction "NC_22") (pintype "passive"))
    )
    (net (code "99") (name "unconnected-(U2-RI-Pad2)") (class "Default")
      (node (ref "U2") (pin "2") (pinfunction "RI_2") (pintype "passive"))
    )
    (net (code "100") (name "unconnected-(U2-SUSPEND-Pad12)") (class "Default")
      (node (ref "U2") (pin "12") (pinfunction "SUSPEND_12") (pintype "passive"))
    )
    (net (code "101") (name "unconnected-(U2-VDD-Pad6)") (class "Default")
      (node (ref "U2") (pin "6") (pinfunction "VDD_6") (pintype "passive"))
    )
    (net (code "102") (name "unconnected-(U4-CAP1_NC-Pad48)") (class "Default")
      (node (ref "U4") (pin "48") (pinfunction "CAP1_NC_48") (pintype "passive"))
    )
    (net (code "103") (name "unconnected-(U4-CAP2_NC-Pad47)") (class "Default")
      (node (ref "U4") (pin "47") (pinfunction "CAP2_NC_47") (pintype "passive"))
    )
    (net (code "104") (name "unconnected-(U4-VDD_SDIO_NC-Pad26)") (class "Default")
      (node (ref "U4") (pin "26") (pinfunction "VDD_SDIO_NC_26") (pintype "passive"))
    )
    (net (code "105") (name "unconnected-(U4-XTAL_N_NC-Pad44)") (class "Default")
      (node (ref "U4") (pin "44") (pinfunction "XTAL_N_NC_44") (pintype "passive"))
    )
    (net (code "106") (name "unconnected-(U4-XTAL_P_NC-Pad45)") (class "Default")
      (node (ref "U4") (pin "45") (pinfunction "XTAL_P_NC_45") (pintype "passive"))
    )
    (net (code "107") (name "unconnected-(USB1-RX1+-PadB11)") (class "Default")
      (node (ref "USB1") (pin "B11") (pinfunction "RX1+_B11") (pintype "passive"))
    )
    (net (code "108") (name "unconnected-(USB1-RX1--PadB10)") (class "Default")
      (node (ref "USB1") (pin "B10") (pinfunction "RX1-_B10") (pintype "passive"))
    )
    (net (code "109") (name "unconnected-(USB1-RX2+-PadA11)") (class "Default")
      (node (ref "USB1") (pin "A11") (pinfunction "RX2+_A11") (pintype "passive"))
    )
    (net (code "110") (name "unconnected-(USB1-RX2--PadA10)") (class "Default")
      (node (ref "USB1") (pin "A10") (pinfunction "RX2-_A10") (pintype "passive"))
    )
    (net (code "111") (name "unconnected-(USB1-SBU1-PadA8)") (class "Default")
      (node (ref "USB1") (pin "A8") (pinfunction "SBU1_A8") (pintype "passive"))
    )
    (net (code "112") (name "unconnected-(USB1-SBU2-PadB8)") (class "Default")
      (node (ref "USB1") (pin "B8") (pinfunction "SBU2_B8") (pintype "passive"))
    )
    (net (code "113") (name "unconnected-(USB1-TX1+-PadA2)") (class "Default")
      (node (ref "USB1") (pin "A2") (pinfunction "TX1+_A2") (pintype "passive"))
    )
    (net (code "114") (name "unconnected-(USB1-TX1--PadA3)") (class "Default")
      (node (ref "USB1") (pin "A3") (pinfunction "TX1-_A3") (pintype "passive"))
    )
    (net (code "115") (name "unconnected-(USB1-TX2+-PadB2)") (class "Default")
      (node (ref "USB1") (pin "B2") (pinfunction "TX2+_B2") (pintype "passive"))
    )
    (net (code "116") (name "unconnected-(USB1-TX2--PadB3)") (class "Default")
      (node (ref "USB1") (pin "B3") (pinfunction "TX2-_B3") (pintype "passive"))
    )
  )
)
